# FPGA1_PMOD_Buffers.net
KiCad netlist of a schematic drawn in Altium Designer
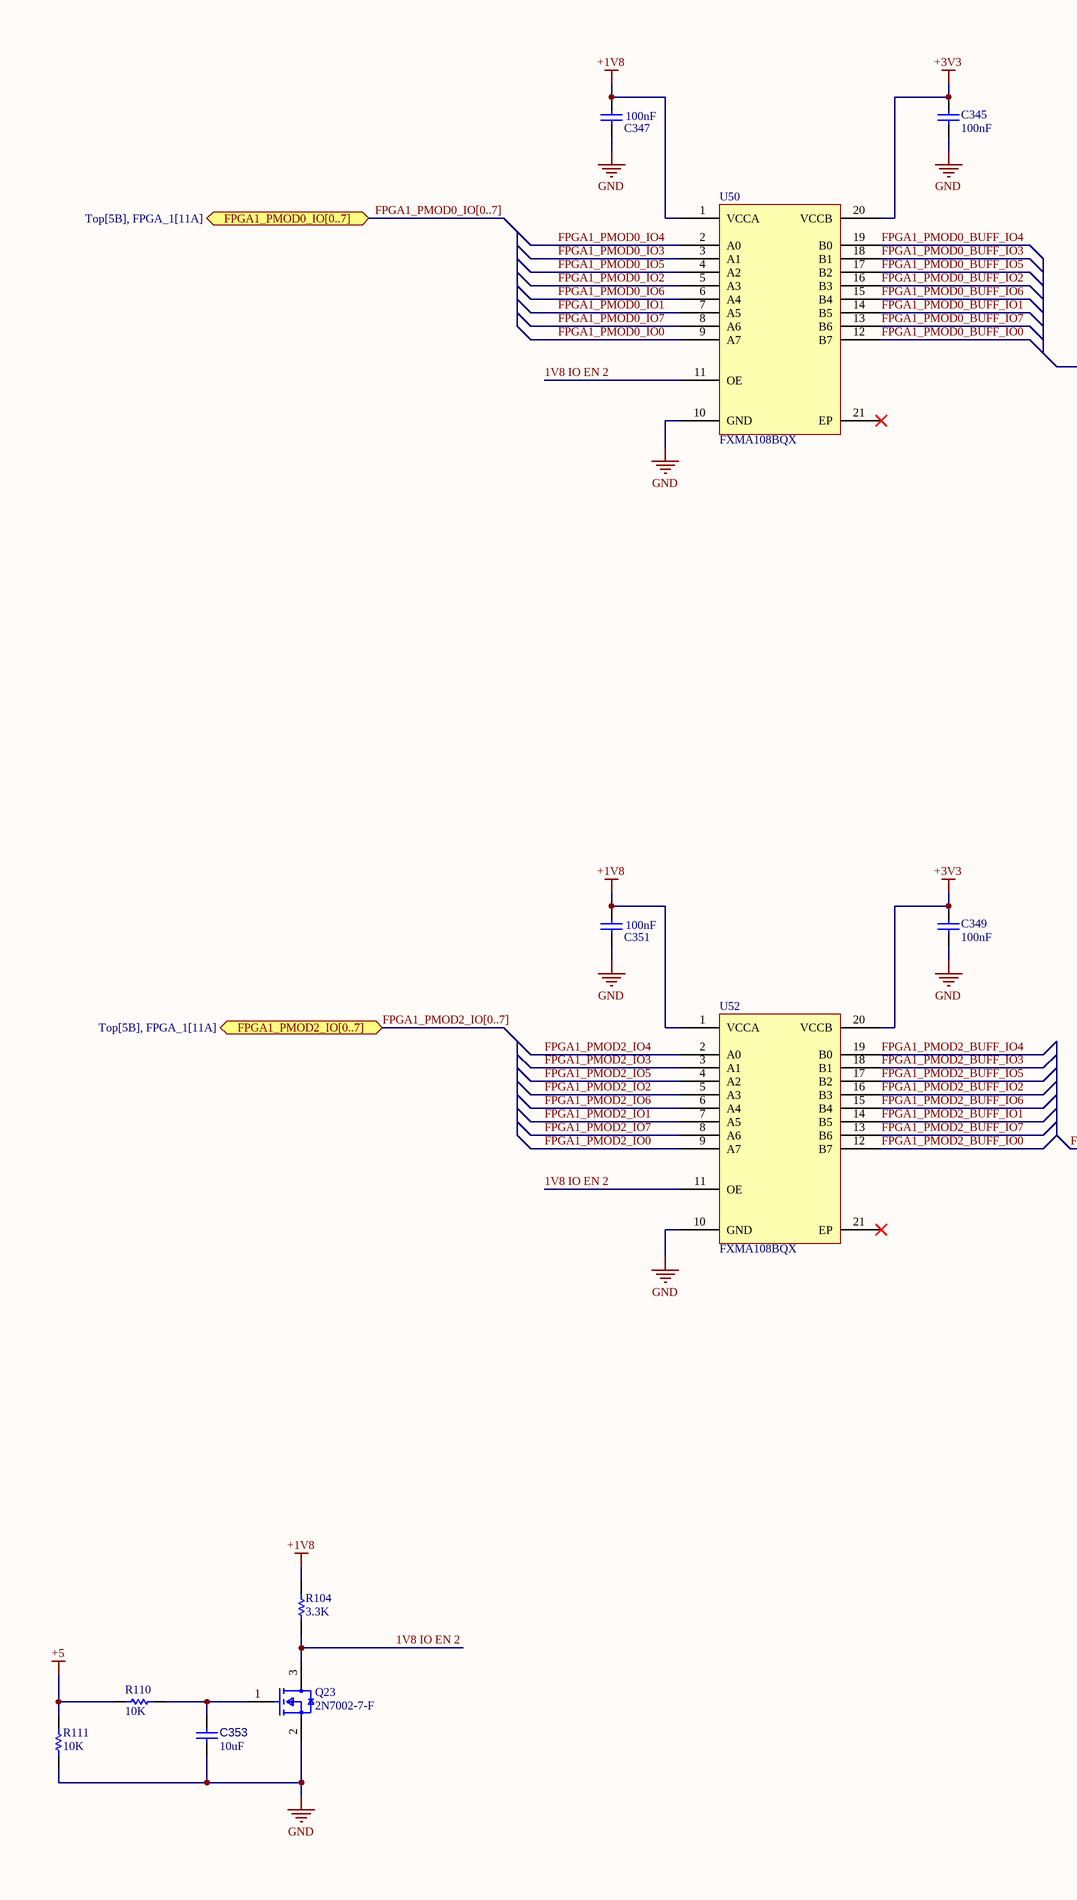
[diagram p0: FPGA1 PMOD Buffers.SchDoc, left]
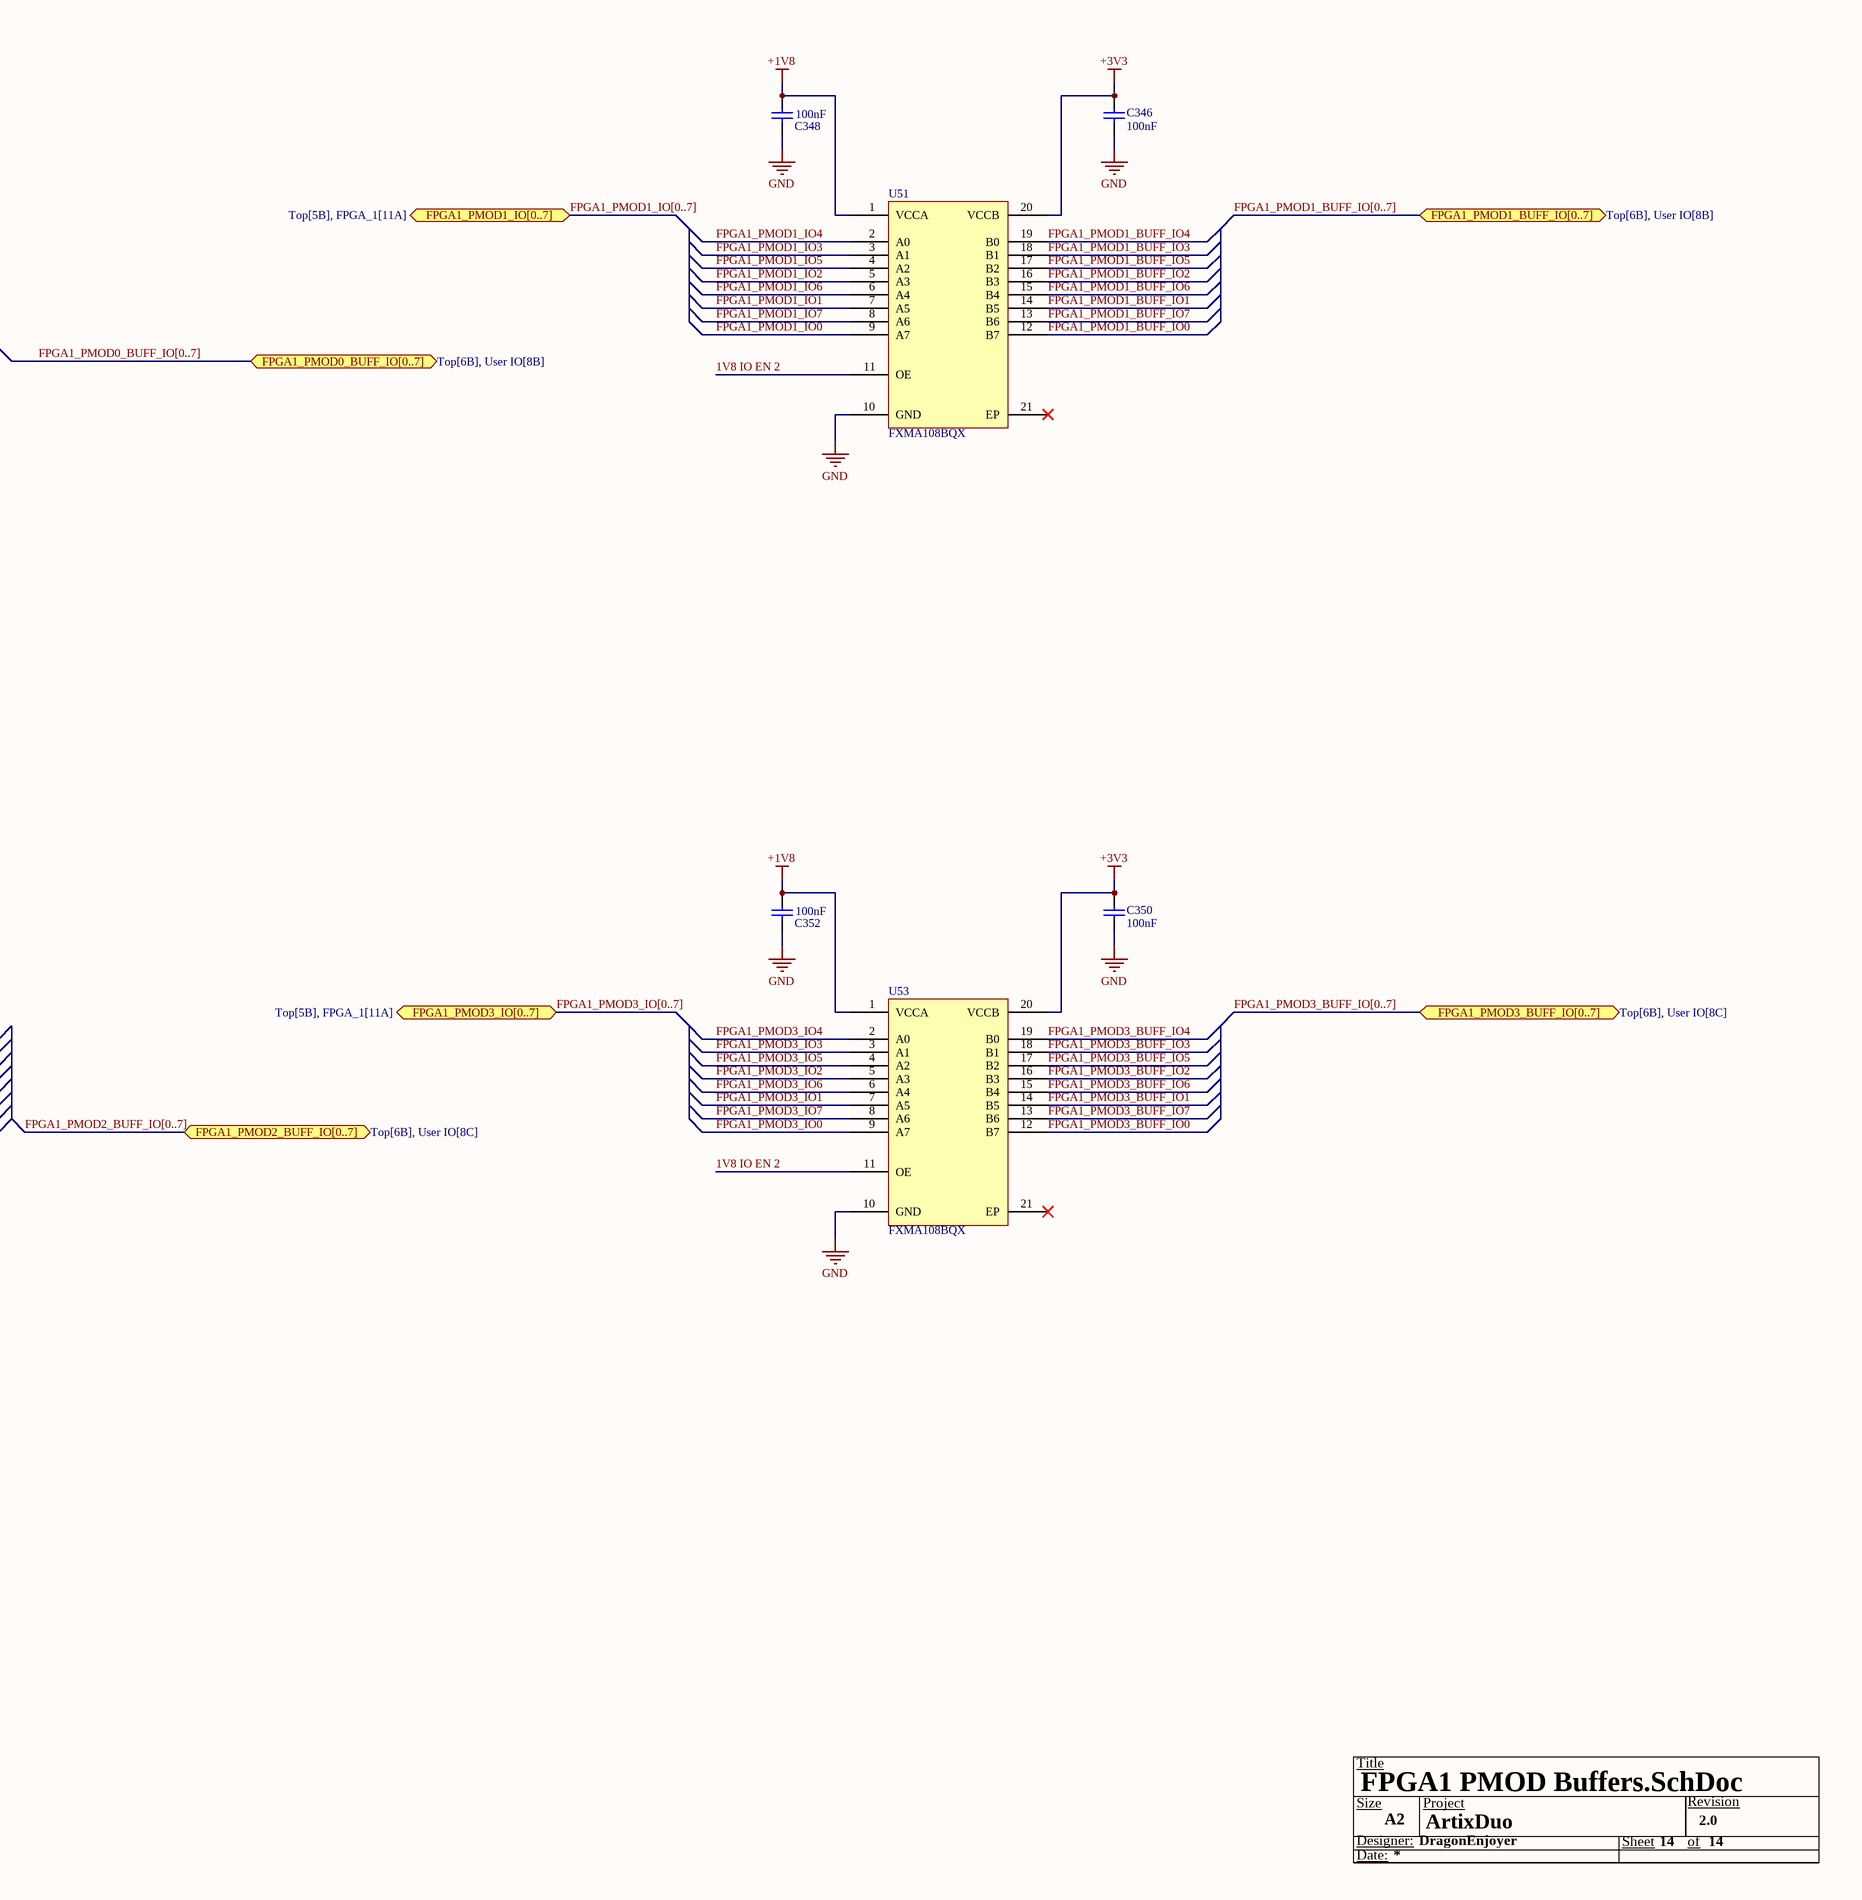
[diagram p1: FPGA1 PMOD Buffers.SchDoc, right]

(export (version "E")
  (design (tool "Eeschema 10.0.6"))
  (components
    (comp (ref "C345")
      (value "100nF")
      (footprint "CAPC1005X05N")
      (description "Cap Ceramic 0.1uF 50V X7R 20% SMD 0402 125°C Paper T/R GRM155R71H104ME14J")
      (fields (field (name "VOLTAGE") "50V"))
      (libsource (lib "Main Workspace") (part "CAP"))
    )
    (comp (ref "C346")
      (value "100nF")
      (footprint "CAPC1005X05N")
      (description "Cap Ceramic 0.1uF 50V X7R 20% SMD 0402 125°C Paper T/R GRM155R71H104ME14J")
      (fields (field (name "VOLTAGE") "50V"))
      (libsource (lib "Main Workspace") (part "CAP"))
    )
    (comp (ref "C347")
      (value "100nF")
      (footprint "CAPC1005X05N")
      (description "Cap Ceramic 0.1uF 50V X7R 20% SMD 0402 125°C Paper T/R GRM155R71H104ME14J")
      (fields (field (name "VOLTAGE") "50V"))
      (libsource (lib "Main Workspace") (part "CAP"))
    )
    (comp (ref "C348")
      (value "100nF")
      (footprint "CAPC1005X05N")
      (description "Cap Ceramic 0.1uF 50V X7R 20% SMD 0402 125°C Paper T/R GRM155R71H104ME14J")
      (fields (field (name "VOLTAGE") "50V"))
      (libsource (lib "Main Workspace") (part "CAP"))
    )
    (comp (ref "C349")
      (value "100nF")
      (footprint "CAPC1005X05N")
      (description "Cap Ceramic 0.1uF 50V X7R 20% SMD 0402 125°C Paper T/R GRM155R71H104ME14J")
      (fields (field (name "VOLTAGE") "50V"))
      (libsource (lib "Main Workspace") (part "CAP"))
    )
    (comp (ref "C350")
      (value "100nF")
      (footprint "CAPC1005X05N")
      (description "Cap Ceramic 0.1uF 50V X7R 20% SMD 0402 125°C Paper T/R GRM155R71H104ME14J")
      (fields (field (name "VOLTAGE") "50V"))
      (libsource (lib "Main Workspace") (part "CAP"))
    )
    (comp (ref "C351")
      (value "100nF")
      (footprint "CAPC1005X05N")
      (description "Cap Ceramic 0.1uF 50V X7R 20% SMD 0402 125°C Paper T/R GRM155R71H104ME14J")
      (fields (field (name "VOLTAGE") "50V"))
      (libsource (lib "Main Workspace") (part "CAP"))
    )
    (comp (ref "C352")
      (value "100nF")
      (footprint "CAPC1005X05N")
      (description "Cap Ceramic 0.1uF 50V X7R 20% SMD 0402 125°C Paper T/R GRM155R71H104ME14J")
      (fields (field (name "VOLTAGE") "50V"))
      (libsource (lib "Main Workspace") (part "CAP"))
    )
    (comp (ref "C353")
      (value "10uF")
      (footprint "CAPC1608X04N")
      (description "CAP CER 10UF 25V X5R 0603")
      (fields (field (name "VOLTAGE") "25V") (field (name "TOLERANCE") "20%"))
      (libsource (lib "Main Workspace") (part "CAP-NP-2"))
    )
    (comp (ref "Q23")
      (value "2N7002-7-F")
      (footprint "FP-SOT23-MFG")
      (description "MOSFET N-CH 60V 115MA SOT23-3")
      (fields (field (name "VOLTAGE") "60V"))
      (libsource (lib "Altium Content Vault") (part "3b9c635fedb024a5347a57b145af9cc"))
    )
    (comp (ref "R104")
      (value "3.3K")
      (footprint "RESC1005X40X25NL05T10")
      (description "CRCW04023K30FKEDHP")
      (fields (field (name "MANUFACTURER") "Vishay Dale"))
      (libsource (lib "Altium Content Vault") (part "RES"))
    )
    (comp (ref "R110")
      (value "10K")
      (footprint "RESC1005X40X25NL05T10")
      (description "RC0402FR-0710KL")
      (fields (field (name "MANUFACTURER") "Yageo / Phycomp"))
      (libsource (lib "Altium Content Vault") (part "RES"))
    )
    (comp (ref "R111")
      (value "10K")
      (footprint "RESC1005X40X25NL05T10")
      (description "RC0402FR-0710KL")
      (fields (field (name "MANUFACTURER") "Yageo / Phycomp"))
      (libsource (lib "Altium Content Vault") (part "RES"))
    )
    (comp (ref "U50")
      (value "FXMA108BQX")
      (footprint "QFN50P450X250X80_HS-21N")
      (description "FXMA108 Series 3.6 V Surface Mount Dual Supply 8-Bit Voltage Translator -DQFN-20")
      (libsource (lib "Main Workspace") (part "FXMA108BQX"))
    )
    (comp (ref "U51")
      (value "FXMA108BQX")
      (footprint "QFN50P450X250X80_HS-21N")
      (description "FXMA108 Series 3.6 V Surface Mount Dual Supply 8-Bit Voltage Translator -DQFN-20")
      (libsource (lib "Main Workspace") (part "FXMA108BQX"))
    )
    (comp (ref "U52")
      (value "FXMA108BQX")
      (footprint "QFN50P450X250X80_HS-21N")
      (description "FXMA108 Series 3.6 V Surface Mount Dual Supply 8-Bit Voltage Translator -DQFN-20")
      (libsource (lib "Main Workspace") (part "FXMA108BQX"))
    )
    (comp (ref "U53")
      (value "FXMA108BQX")
      (footprint "QFN50P450X250X80_HS-21N")
      (description "FXMA108 Series 3.6 V Surface Mount Dual Supply 8-Bit Voltage Translator -DQFN-20")
      (libsource (lib "Main Workspace") (part "FXMA108BQX"))
    )
  )
  (nets
    (net (code "1") (name "+1V8") (class "Default")
      (node (ref "C347") (pin "2") (pinfunction "2_2") (pintype "passive"))
      (node (ref "C348") (pin "2") (pinfunction "2_2") (pintype "passive"))
      (node (ref "C351") (pin "2") (pinfunction "2_2") (pintype "passive"))
      (node (ref "C352") (pin "2") (pinfunction "2_2") (pintype "passive"))
      (node (ref "R104") (pin "2") (pinfunction "2_2") (pintype "passive"))
      (node (ref "U50") (pin "1") (pinfunction "VCCA_1") (pintype "passive"))
      (node (ref "U51") (pin "1") (pinfunction "VCCA_1") (pintype "passive"))
      (node (ref "U52") (pin "1") (pinfunction "VCCA_1") (pintype "passive"))
      (node (ref "U53") (pin "1") (pinfunction "VCCA_1") (pintype "passive"))
    )
    (net (code "2") (name "+3V3") (class "Default")
      (node (ref "C345") (pin "2") (pinfunction "2_2") (pintype "passive"))
      (node (ref "C346") (pin "2") (pinfunction "2_2") (pintype "passive"))
      (node (ref "C349") (pin "2") (pinfunction "2_2") (pintype "passive"))
      (node (ref "C350") (pin "2") (pinfunction "2_2") (pintype "passive"))
      (node (ref "U50") (pin "20") (pinfunction "VCCB_20") (pintype "passive"))
      (node (ref "U51") (pin "20") (pinfunction "VCCB_20") (pintype "passive"))
      (node (ref "U52") (pin "20") (pinfunction "VCCB_20") (pintype "passive"))
      (node (ref "U53") (pin "20") (pinfunction "VCCB_20") (pintype "passive"))
    )
    (net (code "3") (name "+5") (class "Default")
      (node (ref "R110") (pin "2") (pinfunction "2_2") (pintype "passive"))
      (node (ref "R111") (pin "1") (pinfunction "1_1") (pintype "passive"))
    )
    (net (code "4") (name "/1V8 IO EN 2") (class "Default")
      (node (ref "Q23") (pin "3") (pinfunction "D_3") (pintype "passive"))
      (node (ref "R104") (pin "1") (pinfunction "1_1") (pintype "passive"))
      (node (ref "U50") (pin "11") (pinfunction "OE_11") (pintype "passive"))
      (node (ref "U51") (pin "11") (pinfunction "OE_11") (pintype "passive"))
      (node (ref "U52") (pin "11") (pinfunction "OE_11") (pintype "passive"))
      (node (ref "U53") (pin "11") (pinfunction "OE_11") (pintype "passive"))
    )
    (net (code "5") (name "/FPGA1_PMOD0_BUFF_IO0") (class "Default")
      (node (ref "U50") (pin "12") (pinfunction "B7_12") (pintype "passive"))
    )
    (net (code "6") (name "/FPGA1_PMOD0_BUFF_IO1") (class "Default")
      (node (ref "U50") (pin "14") (pinfunction "B5_14") (pintype "passive"))
    )
    (net (code "7") (name "/FPGA1_PMOD0_BUFF_IO2") (class "Default")
      (node (ref "U50") (pin "16") (pinfunction "B3_16") (pintype "passive"))
    )
    (net (code "8") (name "/FPGA1_PMOD0_BUFF_IO3") (class "Default")
      (node (ref "U50") (pin "18") (pinfunction "B1_18") (pintype "passive"))
    )
    (net (code "9") (name "/FPGA1_PMOD0_BUFF_IO4") (class "Default")
      (node (ref "U50") (pin "19") (pinfunction "B0_19") (pintype "passive"))
    )
    (net (code "10") (name "/FPGA1_PMOD0_BUFF_IO5") (class "Default")
      (node (ref "U50") (pin "17") (pinfunction "B2_17") (pintype "passive"))
    )
    (net (code "11") (name "/FPGA1_PMOD0_BUFF_IO6") (class "Default")
      (node (ref "U50") (pin "15") (pinfunction "B4_15") (pintype "passive"))
    )
    (net (code "12") (name "/FPGA1_PMOD0_BUFF_IO7") (class "Default")
      (node (ref "U50") (pin "13") (pinfunction "B6_13") (pintype "passive"))
    )
    (net (code "14") (name "/FPGA1_PMOD0_IO0") (class "Default")
      (node (ref "U50") (pin "9") (pinfunction "A7_9") (pintype "passive"))
    )
    (net (code "15") (name "/FPGA1_PMOD0_IO1") (class "Default")
      (node (ref "U50") (pin "7") (pinfunction "A5_7") (pintype "passive"))
    )
    (net (code "16") (name "/FPGA1_PMOD0_IO2") (class "Default")
      (node (ref "U50") (pin "5") (pinfunction "A3_5") (pintype "passive"))
    )
    (net (code "17") (name "/FPGA1_PMOD0_IO3") (class "Default")
      (node (ref "U50") (pin "3") (pinfunction "A1_3") (pintype "passive"))
    )
    (net (code "18") (name "/FPGA1_PMOD0_IO4") (class "Default")
      (node (ref "U50") (pin "2") (pinfunction "A0_2") (pintype "passive"))
    )
    (net (code "19") (name "/FPGA1_PMOD0_IO5") (class "Default")
      (node (ref "U50") (pin "4") (pinfunction "A2_4") (pintype "passive"))
    )
    (net (code "20") (name "/FPGA1_PMOD0_IO6") (class "Default")
      (node (ref "U50") (pin "6") (pinfunction "A4_6") (pintype "passive"))
    )
    (net (code "21") (name "/FPGA1_PMOD0_IO7") (class "Default")
      (node (ref "U50") (pin "8") (pinfunction "A6_8") (pintype "passive"))
    )
    (net (code "23") (name "/FPGA1_PMOD1_BUFF_IO0") (class "Default")
      (node (ref "U51") (pin "12") (pinfunction "B7_12") (pintype "passive"))
    )
    (net (code "24") (name "/FPGA1_PMOD1_BUFF_IO1") (class "Default")
      (node (ref "U51") (pin "14") (pinfunction "B5_14") (pintype "passive"))
    )
    (net (code "25") (name "/FPGA1_PMOD1_BUFF_IO2") (class "Default")
      (node (ref "U51") (pin "16") (pinfunction "B3_16") (pintype "passive"))
    )
    (net (code "26") (name "/FPGA1_PMOD1_BUFF_IO3") (class "Default")
      (node (ref "U51") (pin "18") (pinfunction "B1_18") (pintype "passive"))
    )
    (net (code "27") (name "/FPGA1_PMOD1_BUFF_IO4") (class "Default")
      (node (ref "U51") (pin "19") (pinfunction "B0_19") (pintype "passive"))
    )
    (net (code "28") (name "/FPGA1_PMOD1_BUFF_IO5") (class "Default")
      (node (ref "U51") (pin "17") (pinfunction "B2_17") (pintype "passive"))
    )
    (net (code "29") (name "/FPGA1_PMOD1_BUFF_IO6") (class "Default")
      (node (ref "U51") (pin "15") (pinfunction "B4_15") (pintype "passive"))
    )
    (net (code "30") (name "/FPGA1_PMOD1_BUFF_IO7") (class "Default")
      (node (ref "U51") (pin "13") (pinfunction "B6_13") (pintype "passive"))
    )
    (net (code "32") (name "/FPGA1_PMOD1_IO0") (class "Default")
      (node (ref "U51") (pin "9") (pinfunction "A7_9") (pintype "passive"))
    )
    (net (code "33") (name "/FPGA1_PMOD1_IO1") (class "Default")
      (node (ref "U51") (pin "7") (pinfunction "A5_7") (pintype "passive"))
    )
    (net (code "34") (name "/FPGA1_PMOD1_IO2") (class "Default")
      (node (ref "U51") (pin "5") (pinfunction "A3_5") (pintype "passive"))
    )
    (net (code "35") (name "/FPGA1_PMOD1_IO3") (class "Default")
      (node (ref "U51") (pin "3") (pinfunction "A1_3") (pintype "passive"))
    )
    (net (code "36") (name "/FPGA1_PMOD1_IO4") (class "Default")
      (node (ref "U51") (pin "2") (pinfunction "A0_2") (pintype "passive"))
    )
    (net (code "37") (name "/FPGA1_PMOD1_IO5") (class "Default")
      (node (ref "U51") (pin "4") (pinfunction "A2_4") (pintype "passive"))
    )
    (net (code "38") (name "/FPGA1_PMOD1_IO6") (class "Default")
      (node (ref "U51") (pin "6") (pinfunction "A4_6") (pintype "passive"))
    )
    (net (code "39") (name "/FPGA1_PMOD1_IO7") (class "Default")
      (node (ref "U51") (pin "8") (pinfunction "A6_8") (pintype "passive"))
    )
    (net (code "41") (name "/FPGA1_PMOD2_BUFF_IO0") (class "Default")
      (node (ref "U52") (pin "12") (pinfunction "B7_12") (pintype "passive"))
    )
    (net (code "42") (name "/FPGA1_PMOD2_BUFF_IO1") (class "Default")
      (node (ref "U52") (pin "14") (pinfunction "B5_14") (pintype "passive"))
    )
    (net (code "43") (name "/FPGA1_PMOD2_BUFF_IO2") (class "Default")
      (node (ref "U52") (pin "16") (pinfunction "B3_16") (pintype "passive"))
    )
    (net (code "44") (name "/FPGA1_PMOD2_BUFF_IO3") (class "Default")
      (node (ref "U52") (pin "18") (pinfunction "B1_18") (pintype "passive"))
    )
    (net (code "45") (name "/FPGA1_PMOD2_BUFF_IO4") (class "Default")
      (node (ref "U52") (pin "19") (pinfunction "B0_19") (pintype "passive"))
    )
    (net (code "46") (name "/FPGA1_PMOD2_BUFF_IO5") (class "Default")
      (node (ref "U52") (pin "17") (pinfunction "B2_17") (pintype "passive"))
    )
    (net (code "47") (name "/FPGA1_PMOD2_BUFF_IO6") (class "Default")
      (node (ref "U52") (pin "15") (pinfunction "B4_15") (pintype "passive"))
    )
    (net (code "48") (name "/FPGA1_PMOD2_BUFF_IO7") (class "Default")
      (node (ref "U52") (pin "13") (pinfunction "B6_13") (pintype "passive"))
    )
    (net (code "50") (name "/FPGA1_PMOD2_IO0") (class "Default")
      (node (ref "U52") (pin "9") (pinfunction "A7_9") (pintype "passive"))
    )
    (net (code "51") (name "/FPGA1_PMOD2_IO1") (class "Default")
      (node (ref "U52") (pin "7") (pinfunction "A5_7") (pintype "passive"))
    )
    (net (code "52") (name "/FPGA1_PMOD2_IO2") (class "Default")
      (node (ref "U52") (pin "5") (pinfunction "A3_5") (pintype "passive"))
    )
    (net (code "53") (name "/FPGA1_PMOD2_IO3") (class "Default")
      (node (ref "U52") (pin "3") (pinfunction "A1_3") (pintype "passive"))
    )
    (net (code "54") (name "/FPGA1_PMOD2_IO4") (class "Default")
      (node (ref "U52") (pin "2") (pinfunction "A0_2") (pintype "passive"))
    )
    (net (code "55") (name "/FPGA1_PMOD2_IO5") (class "Default")
      (node (ref "U52") (pin "4") (pinfunction "A2_4") (pintype "passive"))
    )
    (net (code "56") (name "/FPGA1_PMOD2_IO6") (class "Default")
      (node (ref "U52") (pin "6") (pinfunction "A4_6") (pintype "passive"))
    )
    (net (code "57") (name "/FPGA1_PMOD2_IO7") (class "Default")
      (node (ref "U52") (pin "8") (pinfunction "A6_8") (pintype "passive"))
    )
    (net (code "59") (name "/FPGA1_PMOD3_BUFF_IO0") (class "Default")
      (node (ref "U53") (pin "12") (pinfunction "B7_12") (pintype "passive"))
    )
    (net (code "60") (name "/FPGA1_PMOD3_BUFF_IO1") (class "Default")
      (node (ref "U53") (pin "14") (pinfunction "B5_14") (pintype "passive"))
    )
    (net (code "61") (name "/FPGA1_PMOD3_BUFF_IO2") (class "Default")
      (node (ref "U53") (pin "16") (pinfunction "B3_16") (pintype "passive"))
    )
    (net (code "62") (name "/FPGA1_PMOD3_BUFF_IO3") (class "Default")
      (node (ref "U53") (pin "18") (pinfunction "B1_18") (pintype "passive"))
    )
    (net (code "63") (name "/FPGA1_PMOD3_BUFF_IO4") (class "Default")
      (node (ref "U53") (pin "19") (pinfunction "B0_19") (pintype "passive"))
    )
    (net (code "64") (name "/FPGA1_PMOD3_BUFF_IO5") (class "Default")
      (node (ref "U53") (pin "17") (pinfunction "B2_17") (pintype "passive"))
    )
    (net (code "65") (name "/FPGA1_PMOD3_BUFF_IO6") (class "Default")
      (node (ref "U53") (pin "15") (pinfunction "B4_15") (pintype "passive"))
    )
    (net (code "66") (name "/FPGA1_PMOD3_BUFF_IO7") (class "Default")
      (node (ref "U53") (pin "13") (pinfunction "B6_13") (pintype "passive"))
    )
    (net (code "68") (name "/FPGA1_PMOD3_IO0") (class "Default")
      (node (ref "U53") (pin "9") (pinfunction "A7_9") (pintype "passive"))
    )
    (net (code "69") (name "/FPGA1_PMOD3_IO1") (class "Default")
      (node (ref "U53") (pin "7") (pinfunction "A5_7") (pintype "passive"))
    )
    (net (code "70") (name "/FPGA1_PMOD3_IO2") (class "Default")
      (node (ref "U53") (pin "5") (pinfunction "A3_5") (pintype "passive"))
    )
    (net (code "71") (name "/FPGA1_PMOD3_IO3") (class "Default")
      (node (ref "U53") (pin "3") (pinfunction "A1_3") (pintype "passive"))
    )
    (net (code "72") (name "/FPGA1_PMOD3_IO4") (class "Default")
      (node (ref "U53") (pin "2") (pinfunction "A0_2") (pintype "passive"))
    )
    (net (code "73") (name "/FPGA1_PMOD3_IO5") (class "Default")
      (node (ref "U53") (pin "4") (pinfunction "A2_4") (pintype "passive"))
    )
    (net (code "74") (name "/FPGA1_PMOD3_IO6") (class "Default")
      (node (ref "U53") (pin "6") (pinfunction "A4_6") (pintype "passive"))
    )
    (net (code "75") (name "/FPGA1_PMOD3_IO7") (class "Default")
      (node (ref "U53") (pin "8") (pinfunction "A6_8") (pintype "passive"))
    )
    (net (code "77") (name "GND") (class "Default")
      (node (ref "C345") (pin "1") (pinfunction "1_1") (pintype "passive"))
      (node (ref "C346") (pin "1") (pinfunction "1_1") (pintype "passive"))
      (node (ref "C347") (pin "1") (pinfunction "1_1") (pintype "passive"))
      (node (ref "C348") (pin "1") (pinfunction "1_1") (pintype "passive"))
      (node (ref "C349") (pin "1") (pinfunction "1_1") (pintype "passive"))
      (node (ref "C350") (pin "1") (pinfunction "1_1") (pintype "passive"))
      (node (ref "C351") (pin "1") (pinfunction "1_1") (pintype "passive"))
      (node (ref "C352") (pin "1") (pinfunction "1_1") (pintype "passive"))
      (node (ref "C353") (pin "1") (pinfunction "1_1") (pintype "passive"))
      (node (ref "Q23") (pin "2") (pinfunction "S_2") (pintype "passive"))
      (node (ref "R111") (pin "2") (pinfunction "2_2") (pintype "passive"))
      (node (ref "U50") (pin "10") (pinfunction "GND_10") (pintype "passive"))
      (node (ref "U51") (pin "10") (pinfunction "GND_10") (pintype "passive"))
      (node (ref "U52") (pin "10") (pinfunction "GND_10") (pintype "passive"))
      (node (ref "U53") (pin "10") (pinfunction "GND_10") (pintype "passive"))
    )
    (net (code "78") (name "Net-(Q23-G)") (class "Default")
      (node (ref "C353") (pin "2") (pinfunction "2_2") (pintype "passive"))
      (node (ref "Q23") (pin "1") (pinfunction "G_1") (pintype "passive"))
      (node (ref "R110") (pin "1") (pinfunction "1_1") (pintype "passive"))
    )
    (net (code "79") (name "unconnected-(U50-EP-Pad21)") (class "Default")
      (node (ref "U50") (pin "21") (pinfunction "EP_21") (pintype "passive+no_connect"))
    )
    (net (code "80") (name "unconnected-(U51-EP-Pad21)") (class "Default")
      (node (ref "U51") (pin "21") (pinfunction "EP_21") (pintype "passive+no_connect"))
    )
    (net (code "81") (name "unconnected-(U52-EP-Pad21)") (class "Default")
      (node (ref "U52") (pin "21") (pinfunction "EP_21") (pintype "passive+no_connect"))
    )
    (net (code "82") (name "unconnected-(U53-EP-Pad21)") (class "Default")
      (node (ref "U53") (pin "21") (pinfunction "EP_21") (pintype "passive+no_connect"))
    )
  )
)
